# ece411-t17-thermal-hud.net
KiCad netlist of a schematic drawn in EAGLE
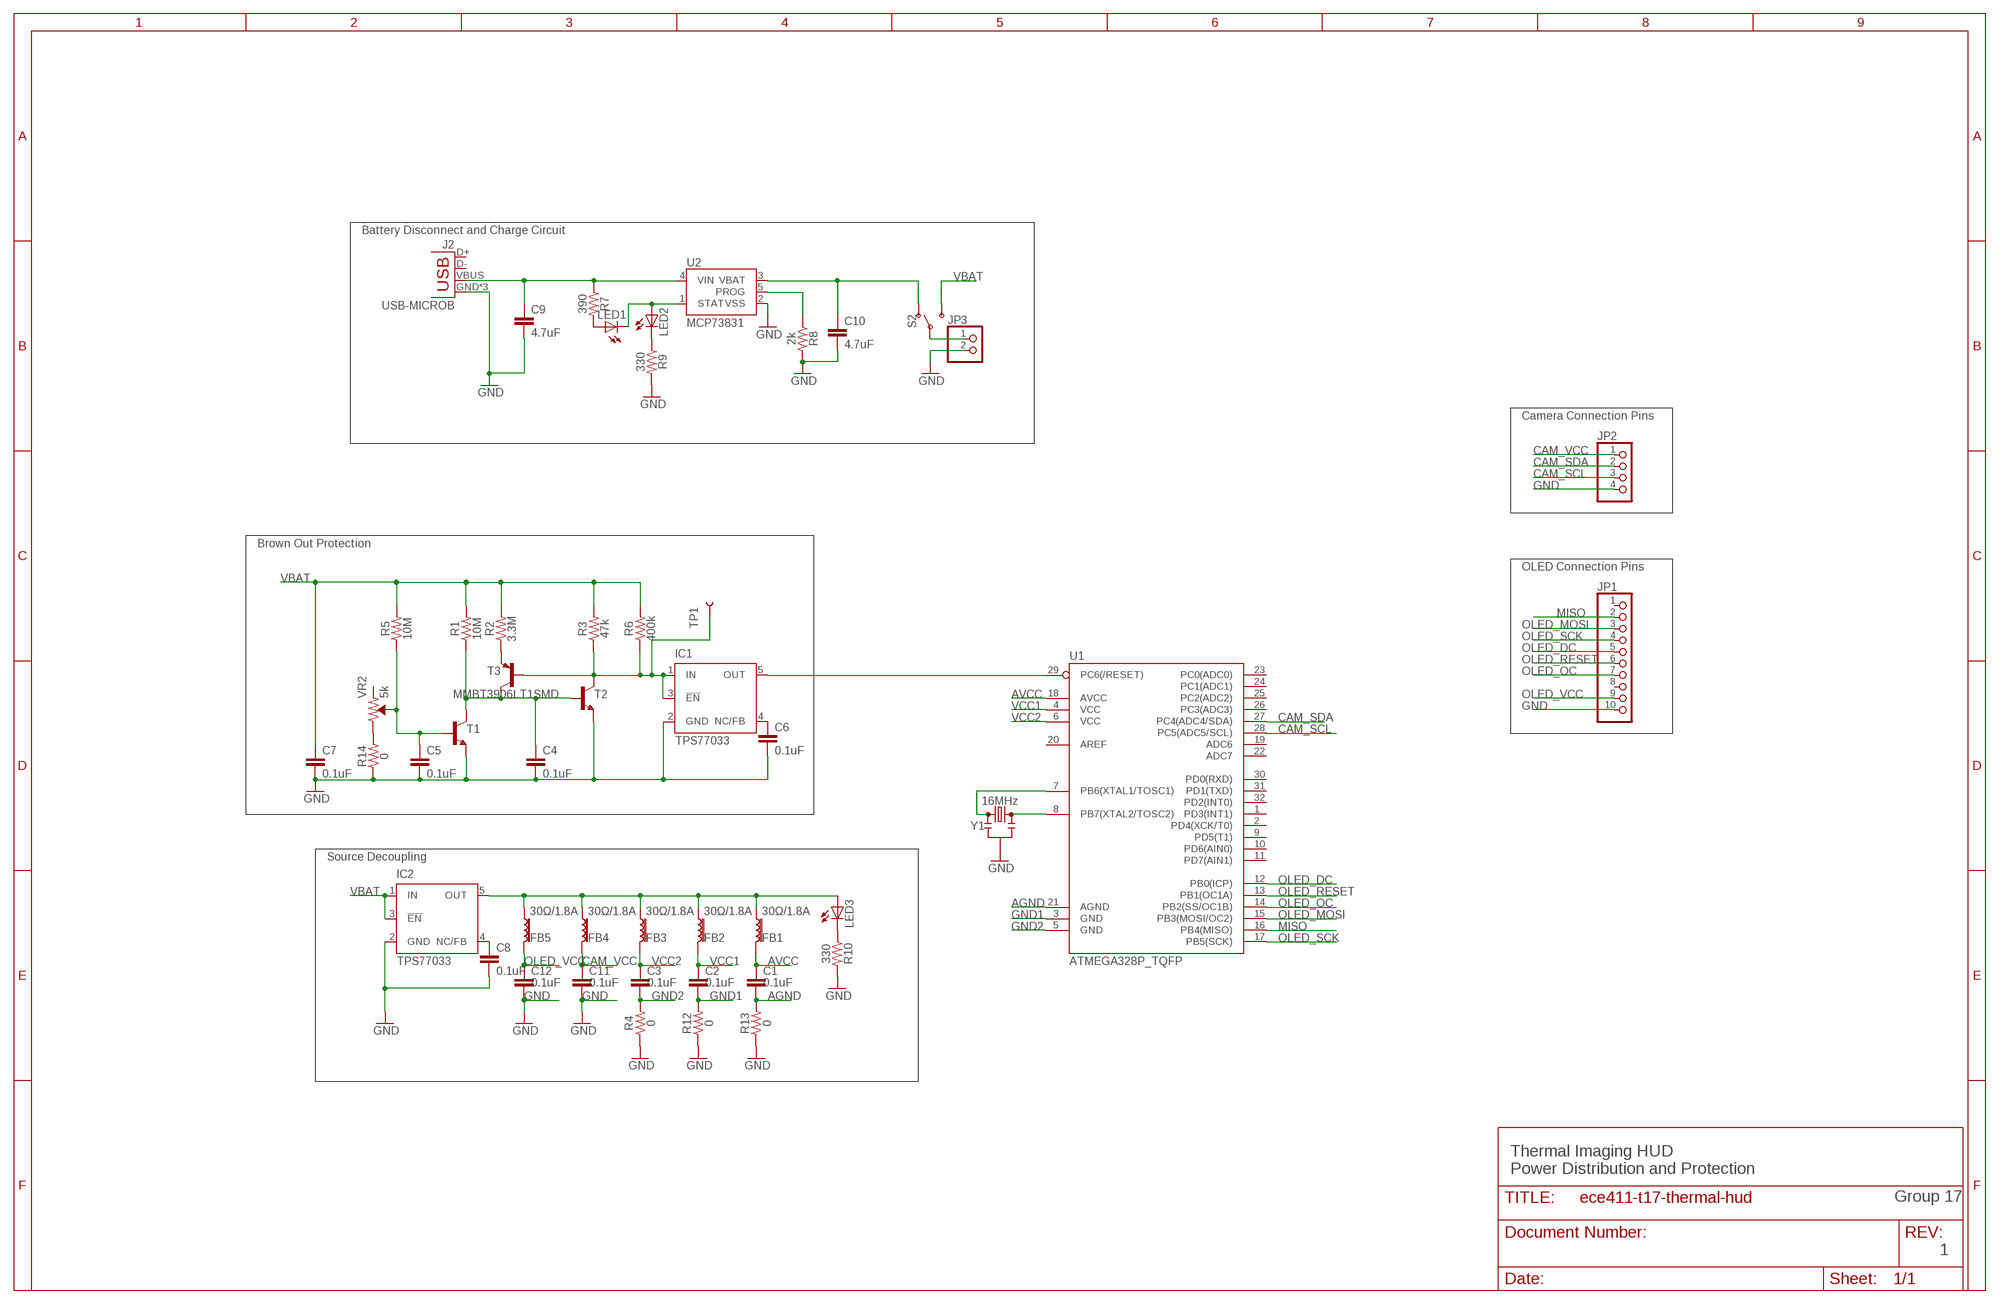
[diagram p0: schematic, sheet 1]

(export (version "E")
  (design (tool "Eeschema 10.0.6"))
  (components
    (comp (ref "C1")
      (value "0.1uF")
      (footprint "eagle-import:0603")
      (libsource (lib "eagle-import") (part "0.1UF-0603-25V-5%"))
    )
    (comp (ref "C2")
      (value "0.1uF")
      (footprint "eagle-import:0603")
      (libsource (lib "eagle-import") (part "0.1UF-0603-25V-5%"))
    )
    (comp (ref "C3")
      (value "0.1uF")
      (footprint "eagle-import:0603")
      (libsource (lib "eagle-import") (part "0.1UF-0603-25V-5%"))
    )
    (comp (ref "C4")
      (value "0.1uF")
      (footprint "eagle-import:0603")
      (libsource (lib "eagle-import") (part "0.1UF-0603-25V-5%"))
    )
    (comp (ref "C5")
      (value "0.1uF")
      (footprint "eagle-import:0603")
      (libsource (lib "eagle-import") (part "0.1UF-0603-25V-5%"))
    )
    (comp (ref "C6")
      (value "0.1uF")
      (footprint "eagle-import:0603")
      (libsource (lib "eagle-import") (part "0.1UF-0603-25V-5%"))
    )
    (comp (ref "C7")
      (value "0.1uF")
      (footprint "eagle-import:0603")
      (libsource (lib "eagle-import") (part "0.1UF-0603-25V-5%"))
    )
    (comp (ref "C8")
      (value "0.1uF")
      (footprint "eagle-import:0603")
      (libsource (lib "eagle-import") (part "0.1UF-0603-25V-5%"))
    )
    (comp (ref "C9")
      (value "4.7uF")
      (footprint "eagle-import:0603")
      (libsource (lib "eagle-import") (part "0.1UF-0603-25V-5%"))
    )
    (comp (ref "C10")
      (value "4.7uF")
      (footprint "eagle-import:0603")
      (libsource (lib "eagle-import") (part "0.1UF-0603-25V-5%"))
    )
    (comp (ref "C11")
      (value "0.1uF")
      (footprint "eagle-import:0603")
      (libsource (lib "eagle-import") (part "0.1UF-0603-25V-5%"))
    )
    (comp (ref "C12")
      (value "0.1uF")
      (footprint "eagle-import:0603")
      (libsource (lib "eagle-import") (part "0.1UF-0603-25V-5%"))
    )
    (comp (ref "FB1")
      (value "30Ω/1.8A")
      (footprint "eagle-import:0603")
      (libsource (lib "eagle-import") (part "FERRITE_BEAD-0603"))
    )
    (comp (ref "FB2")
      (value "30Ω/1.8A")
      (footprint "eagle-import:0603")
      (libsource (lib "eagle-import") (part "FERRITE_BEAD-0603"))
    )
    (comp (ref "FB3")
      (value "30Ω/1.8A")
      (footprint "eagle-import:0603")
      (libsource (lib "eagle-import") (part "FERRITE_BEAD-0603"))
    )
    (comp (ref "FB4")
      (value "30Ω/1.8A")
      (footprint "eagle-import:0603")
      (libsource (lib "eagle-import") (part "FERRITE_BEAD-0603"))
    )
    (comp (ref "FB5")
      (value "30Ω/1.8A")
      (footprint "eagle-import:0603")
      (libsource (lib "eagle-import") (part "FERRITE_BEAD-0603"))
    )
    (comp (ref "IC1")
      (value "TPS77033")
      (footprint "eagle-import:SOT23-DBV")
      (fields (field (name "MF") "TEXAS INSTRUMENTS") (field (name "MPN") "TPS77033DBVT"))
      (libsource (lib "eagle-import") (part "TPS77033"))
    )
    (comp (ref "IC2")
      (value "TPS77033")
      (footprint "eagle-import:SOT23-DBV")
      (fields (field (name "MF") "TEXAS INSTRUMENTS") (field (name "MPN") "TPS77033DBVT"))
      (libsource (lib "eagle-import") (part "TPS77033"))
    )
    (comp (ref "J2")
      (value "USB-MICROB")
      (footprint "eagle-import:USB-MICROB")
      (libsource (lib "eagle-import") (part "USB-MICROB"))
    )
    (comp (ref "JP1")
      (value "PINHD-1X10/90")
      (footprint "eagle-import:1X10_90")
      (libsource (lib "eagle-import") (part "PINHD-1X10/90"))
    )
    (comp (ref "JP2")
      (value "PINHD-1X4/90")
      (footprint "eagle-import:1X04_90")
      (libsource (lib "eagle-import") (part "PINHD-1X4/90"))
    )
    (comp (ref "JP3")
      (value "PINHD-1X2/90")
      (footprint "eagle-import:1X02_90")
      (libsource (lib "eagle-import") (part "PINHD-1X2/90"))
    )
    (comp (ref "LED1")
      (value "LEDCHIPLED_0603")
      (footprint "eagle-import:CHIPLED_0603")
      (libsource (lib "eagle-import") (part "LEDCHIPLED_0603"))
    )
    (comp (ref "LED2")
      (value "LEDCHIPLED_0603")
      (footprint "eagle-import:CHIPLED_0603")
      (libsource (lib "eagle-import") (part "LEDCHIPLED_0603"))
    )
    (comp (ref "LED3")
      (value "LEDCHIPLED_0603")
      (footprint "eagle-import:CHIPLED_0603")
      (libsource (lib "eagle-import") (part "LEDCHIPLED_0603"))
    )
    (comp (ref "R1")
      (value "10M")
      (footprint "eagle-import:0603")
      (libsource (lib "eagle-import") (part "10MOHM-0603-1/10W-5%"))
    )
    (comp (ref "R2")
      (value "3.3M")
      (footprint "eagle-import:0603")
      (libsource (lib "eagle-import") (part "10MOHM-0603-1/10W-5%"))
    )
    (comp (ref "R3")
      (value "47k")
      (footprint "eagle-import:0603")
      (libsource (lib "eagle-import") (part "10MOHM-0603-1/10W-5%"))
    )
    (comp (ref "R4")
      (value "0")
      (footprint "eagle-import:0603")
      (libsource (lib "eagle-import") (part "0OHM-0603-1/10W-5%"))
    )
    (comp (ref "R5")
      (value "10M")
      (footprint "eagle-import:0603")
      (libsource (lib "eagle-import") (part "10MOHM-0603-1/10W-5%"))
    )
    (comp (ref "R6")
      (value "400k")
      (footprint "eagle-import:0603")
      (libsource (lib "eagle-import") (part "10MOHM-0603-1/10W-5%"))
    )
    (comp (ref "R7")
      (value "390")
      (footprint "eagle-import:0603")
      (libsource (lib "eagle-import") (part "10MOHM-0603-1/10W-5%"))
    )
    (comp (ref "R8")
      (value "2k")
      (footprint "eagle-import:0603")
      (libsource (lib "eagle-import") (part "10MOHM-0603-1/10W-5%"))
    )
    (comp (ref "R9")
      (value "330")
      (footprint "eagle-import:0603")
      (libsource (lib "eagle-import") (part "10MOHM-0603-1/10W-5%"))
    )
    (comp (ref "R10")
      (value "330")
      (footprint "eagle-import:0603")
      (libsource (lib "eagle-import") (part "10MOHM-0603-1/10W-5%"))
    )
    (comp (ref "R12")
      (value "0")
      (footprint "eagle-import:0603")
      (libsource (lib "eagle-import") (part "0OHM-0603-1/10W-5%"))
    )
    (comp (ref "R13")
      (value "0")
      (footprint "eagle-import:0603")
      (libsource (lib "eagle-import") (part "0OHM-0603-1/10W-5%"))
    )
    (comp (ref "R14")
      (value "0")
      (footprint "eagle-import:0603")
      (libsource (lib "eagle-import") (part "0OHM-0603-1/10W-5%"))
    )
    (comp (ref "S2")
      (value "SWITCH-SPDT-PTH-11.6X4.0MM")
      (footprint "eagle-import:SWITCH_SPDT_PTH_11.6X4.0MM")
      (libsource (lib "eagle-import") (part "SWITCH-SPDT-PTH-11.6X4.0MM"))
    )
    (comp (ref "T1")
      (value "MMBT3904LT1-NPN-SOT23-BEC")
      (footprint "eagle-import:SOT23-BEC")
      (libsource (lib "eagle-import") (part "-NPN-SOT23-BECMMBT3904LT1"))
    )
    (comp (ref "T2")
      (value "MMBT3904LT1-NPN-SOT23-BEC")
      (footprint "eagle-import:SOT23-BEC")
      (libsource (lib "eagle-import") (part "-NPN-SOT23-BECMMBT3904LT1"))
    )
    (comp (ref "T3")
      (value "MMBT3906LT1SMD")
      (footprint "eagle-import:SOT23-BEC")
      (libsource (lib "eagle-import") (part "MMBT3906SMDLT1"))
    )
    (comp (ref "TP1")
      (value "TEST-POINT3X5")
      (footprint "eagle-import:PAD.03X.05")
      (libsource (lib "eagle-import") (part "TEST-POINT3X5"))
    )
    (comp (ref "U1")
      (value "ATMEGA328P_TQFP")
      (footprint "eagle-import:TQFP32-08")
      (libsource (lib "eagle-import") (part "ATMEGA328P_TQFP"))
    )
    (comp (ref "U2")
      (value "MCP73831")
      (footprint "eagle-import:SOT23-5")
      (libsource (lib "eagle-import") (part "MCP73831"))
    )
    (comp (ref "VR2")
      (value "5k")
      (footprint "eagle-import:TRIMPOT-SMD-5MM")
      (libsource (lib "eagle-import") (part "TRIMPOT-SMD-5MM-CLOSED-1/4W-20%"))
    )
    (comp (ref "Y1")
      (value "16MHz")
      (footprint "eagle-import:RESONATOR-SMD-3.2X1.3")
      (libsource (lib "eagle-import") (part "RESONATOR-16MHZSMD_3.2X1.3"))
    )
  )
  (nets
    (net (code "1") (name "/AGND") (class "Default")
      (node (ref "C1") (pin "2") (pinfunction "2_2") (pintype "passive"))
      (node (ref "R13") (pin "2") (pinfunction "2_2") (pintype "passive"))
      (node (ref "U1") (pin "21") (pinfunction "AGND_21") (pintype "bidirectional"))
    )
    (net (code "2") (name "/AVCC") (class "Default")
      (node (ref "C1") (pin "1") (pinfunction "1_1") (pintype "passive"))
      (node (ref "FB1") (pin "2") (pinfunction "2_2") (pintype "passive"))
      (node (ref "U1") (pin "18") (pinfunction "AVCC_18") (pintype "bidirectional"))
    )
    (net (code "3") (name "/CAM_SCL") (class "Default")
      (node (ref "JP2") (pin "3") (pinfunction "3_3") (pintype "passive"))
      (node (ref "U1") (pin "28") (pinfunction "PC5(ADC5/SCL)_28") (pintype "bidirectional"))
    )
    (net (code "4") (name "/CAM_SDA") (class "Default")
      (node (ref "JP2") (pin "2") (pinfunction "2_2") (pintype "passive"))
      (node (ref "U1") (pin "27") (pinfunction "PC4(ADC4/SDA)_27") (pintype "bidirectional"))
    )
    (net (code "5") (name "/CAM_VCC") (class "Default")
      (node (ref "C11") (pin "1") (pinfunction "1_1") (pintype "passive"))
      (node (ref "FB4") (pin "2") (pinfunction "2_2") (pintype "passive"))
      (node (ref "JP2") (pin "1") (pinfunction "1_1") (pintype "passive"))
    )
    (net (code "6") (name "/GND1") (class "Default")
      (node (ref "C2") (pin "2") (pinfunction "2_2") (pintype "passive"))
      (node (ref "R12") (pin "2") (pinfunction "2_2") (pintype "passive"))
      (node (ref "U1") (pin "3") (pinfunction "GND_3") (pintype "bidirectional"))
    )
    (net (code "7") (name "/GND2") (class "Default")
      (node (ref "C3") (pin "2") (pinfunction "2_2") (pintype "passive"))
      (node (ref "R4") (pin "2") (pinfunction "2_2") (pintype "passive"))
      (node (ref "U1") (pin "5") (pinfunction "GND_5") (pintype "bidirectional"))
    )
    (net (code "8") (name "/MISO") (class "Default")
      (node (ref "JP1") (pin "2") (pinfunction "2_2") (pintype "passive"))
      (node (ref "U1") (pin "16") (pinfunction "PB4(MISO)_16") (pintype "bidirectional"))
    )
    (net (code "9") (name "/OLED_DC") (class "Default")
      (node (ref "JP1") (pin "5") (pinfunction "5_5") (pintype "passive"))
      (node (ref "U1") (pin "12") (pinfunction "PB0(ICP)_12") (pintype "bidirectional"))
    )
    (net (code "10") (name "/OLED_MOSI") (class "Default")
      (node (ref "JP1") (pin "3") (pinfunction "3_3") (pintype "passive"))
      (node (ref "U1") (pin "15") (pinfunction "PB3(MOSI/OC2)_15") (pintype "bidirectional"))
    )
    (net (code "11") (name "/OLED_OC") (class "Default")
      (node (ref "JP1") (pin "7") (pinfunction "7_7") (pintype "passive"))
      (node (ref "U1") (pin "14") (pinfunction "PB2(SS/OC1B)_14") (pintype "bidirectional"))
    )
    (net (code "12") (name "/OLED_RESET") (class "Default")
      (node (ref "JP1") (pin "6") (pinfunction "6_6") (pintype "passive"))
      (node (ref "U1") (pin "13") (pinfunction "PB1(OC1A)_13") (pintype "bidirectional"))
    )
    (net (code "13") (name "/OLED_SCK") (class "Default")
      (node (ref "JP1") (pin "4") (pinfunction "4_4") (pintype "passive"))
      (node (ref "U1") (pin "17") (pinfunction "PB5(SCK)_17") (pintype "bidirectional"))
    )
    (net (code "14") (name "/OLED_VCC") (class "Default")
      (node (ref "C12") (pin "1") (pinfunction "1_1") (pintype "passive"))
      (node (ref "FB5") (pin "2") (pinfunction "2_2") (pintype "passive"))
      (node (ref "JP1") (pin "9") (pinfunction "9_9") (pintype "passive"))
    )
    (net (code "15") (name "/VBAT") (class "Default")
      (node (ref "C7") (pin "1") (pinfunction "1_1") (pintype "passive"))
      (node (ref "IC2") (pin "1") (pinfunction "IN_1") (pintype "input"))
      (node (ref "IC2") (pin "3") (pinfunction "~{EN}_3") (pintype "input"))
      (node (ref "R1") (pin "2") (pinfunction "2_2") (pintype "passive"))
      (node (ref "R2") (pin "2") (pinfunction "2_2") (pintype "passive"))
      (node (ref "R3") (pin "2") (pinfunction "2_2") (pintype "passive"))
      (node (ref "R5") (pin "2") (pinfunction "2_2") (pintype "passive"))
      (node (ref "R6") (pin "2") (pinfunction "2_2") (pintype "passive"))
      (node (ref "S2") (pin "3") (pinfunction "S_3") (pintype "passive"))
    )
    (net (code "16") (name "/VCC1") (class "Default")
      (node (ref "C2") (pin "1") (pinfunction "1_1") (pintype "passive"))
      (node (ref "FB2") (pin "2") (pinfunction "2_2") (pintype "passive"))
      (node (ref "U1") (pin "4") (pinfunction "VCC_4") (pintype "bidirectional"))
    )
    (net (code "17") (name "/VCC2") (class "Default")
      (node (ref "C3") (pin "1") (pinfunction "1_1") (pintype "passive"))
      (node (ref "FB3") (pin "2") (pinfunction "2_2") (pintype "passive"))
      (node (ref "U1") (pin "6") (pinfunction "VCC_6") (pintype "bidirectional"))
    )
    (net (code "18") (name "GND") (class "Default")
      (node (ref "C10") (pin "2") (pinfunction "2_2") (pintype "passive"))
      (node (ref "C11") (pin "2") (pinfunction "2_2") (pintype "passive"))
      (node (ref "C12") (pin "2") (pinfunction "2_2") (pintype "passive"))
      (node (ref "C4") (pin "2") (pinfunction "2_2") (pintype "passive"))
      (node (ref "C5") (pin "2") (pinfunction "2_2") (pintype "passive"))
      (node (ref "C6") (pin "2") (pinfunction "2_2") (pintype "passive"))
      (node (ref "C7") (pin "2") (pinfunction "2_2") (pintype "passive"))
      (node (ref "C8") (pin "2") (pinfunction "2_2") (pintype "passive"))
      (node (ref "C9") (pin "2") (pinfunction "2_2") (pintype "passive"))
      (node (ref "IC1") (pin "2") (pinfunction "GND_2") (pintype "power_in"))
      (node (ref "IC2") (pin "2") (pinfunction "GND_2") (pintype "power_in"))
      (node (ref "J2") (pin "GND") (pinfunction "GND_GND") (pintype "bidirectional"))
      (node (ref "J2") (pin "MT1") (pinfunction "GND_MT1") (pintype "bidirectional"))
      (node (ref "J2") (pin "MT2") (pinfunction "GND_MT2") (pintype "bidirectional"))
      (node (ref "JP1") (pin "10") (pinfunction "10_10") (pintype "passive"))
      (node (ref "JP2") (pin "4") (pinfunction "4_4") (pintype "passive"))
      (node (ref "JP3") (pin "2") (pinfunction "2_2") (pintype "passive"))
      (node (ref "R10") (pin "2") (pinfunction "2_2") (pintype "passive"))
      (node (ref "R12") (pin "1") (pinfunction "1_1") (pintype "passive"))
      (node (ref "R13") (pin "1") (pinfunction "1_1") (pintype "passive"))
      (node (ref "R14") (pin "1") (pinfunction "1_1") (pintype "passive"))
      (node (ref "R4") (pin "1") (pinfunction "1_1") (pintype "passive"))
      (node (ref "R8") (pin "2") (pinfunction "2_2") (pintype "passive"))
      (node (ref "R9") (pin "2") (pinfunction "2_2") (pintype "passive"))
      (node (ref "T1") (pin "E") (pinfunction "E_E") (pintype "passive"))
      (node (ref "T2") (pin "E") (pinfunction "E_E") (pintype "passive"))
      (node (ref "U2") (pin "2") (pinfunction "VSS_2") (pintype "power_in"))
      (node (ref "Y1") (pin "2") (pinfunction "2_2") (pintype "passive"))
    )
    (net (code "19") (name "Net-(C4-Pad1)") (class "Default")
      (node (ref "C4") (pin "1") (pinfunction "1_1") (pintype "passive"))
      (node (ref "R1") (pin "1") (pinfunction "1_1") (pintype "passive"))
      (node (ref "T1") (pin "C") (pinfunction "C_C") (pintype "passive"))
      (node (ref "T2") (pin "B") (pinfunction "B_B") (pintype "passive"))
      (node (ref "T3") (pin "C") (pinfunction "C_C") (pintype "passive"))
    )
    (net (code "20") (name "Net-(IC1-IN)") (class "Default")
      (node (ref "IC1") (pin "1") (pinfunction "IN_1") (pintype "input"))
      (node (ref "IC1") (pin "3") (pinfunction "~{EN}_3") (pintype "input"))
      (node (ref "R3") (pin "1") (pinfunction "1_1") (pintype "passive"))
      (node (ref "R6") (pin "1") (pinfunction "1_1") (pintype "passive"))
      (node (ref "T2") (pin "C") (pinfunction "C_C") (pintype "passive"))
      (node (ref "T3") (pin "B") (pinfunction "B_B") (pintype "passive"))
      (node (ref "TP1") (pin "P$1") (pinfunction "1_P$1") (pintype "bidirectional"))
    )
    (net (code "21") (name "Net-(IC1-NC{slash}FB)") (class "Default")
      (node (ref "C6") (pin "1") (pinfunction "1_1") (pintype "passive"))
      (node (ref "IC1") (pin "4") (pinfunction "NC/FB_4") (pintype "passive"))
    )
    (net (code "22") (name "Net-(IC1-OUT)") (class "Default")
      (node (ref "IC1") (pin "5") (pinfunction "OUT_5") (pintype "passive"))
      (node (ref "U1") (pin "29") (pinfunction "PC6(/RESET)_29") (pintype "bidirectional"))
    )
    (net (code "23") (name "Net-(IC2-NC{slash}FB)") (class "Default")
      (node (ref "C8") (pin "1") (pinfunction "1_1") (pintype "passive"))
      (node (ref "IC2") (pin "4") (pinfunction "NC/FB_4") (pintype "passive"))
    )
    (net (code "24") (name "Net-(IC2-OUT)") (class "Default")
      (node (ref "FB1") (pin "1") (pinfunction "1_1") (pintype "passive"))
      (node (ref "FB2") (pin "1") (pinfunction "1_1") (pintype "passive"))
      (node (ref "FB3") (pin "1") (pinfunction "1_1") (pintype "passive"))
      (node (ref "FB4") (pin "1") (pinfunction "1_1") (pintype "passive"))
      (node (ref "FB5") (pin "1") (pinfunction "1_1") (pintype "passive"))
      (node (ref "IC2") (pin "5") (pinfunction "OUT_5") (pintype "passive"))
      (node (ref "LED3") (pin "A") (pinfunction "A_A") (pintype "passive"))
    )
    (net (code "25") (name "Net-(LED1-PadA)") (class "Default")
      (node (ref "LED1") (pin "A") (pinfunction "A_A") (pintype "passive"))
      (node (ref "R7") (pin "2") (pinfunction "2_2") (pintype "passive"))
    )
    (net (code "26") (name "Net-(LED2-PadC)") (class "Default")
      (node (ref "LED2") (pin "C") (pinfunction "C_C") (pintype "passive"))
      (node (ref "R9") (pin "1") (pinfunction "1_1") (pintype "passive"))
    )
    (net (code "27") (name "Net-(LED3-PadC)") (class "Default")
      (node (ref "LED3") (pin "C") (pinfunction "C_C") (pintype "passive"))
      (node (ref "R10") (pin "1") (pinfunction "1_1") (pintype "passive"))
    )
    (net (code "28") (name "Net-(R2-Pad1)") (class "Default")
      (node (ref "R2") (pin "1") (pinfunction "1_1") (pintype "passive"))
      (node (ref "T3") (pin "E") (pinfunction "E_E") (pintype "passive"))
    )
    (net (code "29") (name "Net-(S2-O)") (class "Default")
      (node (ref "C10") (pin "1") (pinfunction "1_1") (pintype "passive"))
      (node (ref "S2") (pin "1") (pinfunction "O_1") (pintype "passive"))
      (node (ref "U2") (pin "3") (pinfunction "VBAT_3") (pintype "power_in"))
    )
    (net (code "30") (name "Net-(S2-P)") (class "Default")
      (node (ref "JP3") (pin "1") (pinfunction "1_1") (pintype "passive"))
      (node (ref "S2") (pin "2") (pinfunction "P_2") (pintype "passive"))
    )
    (net (code "31") (name "Net-(U1-PB6(XTAL1{slash}TOSC1))") (class "Default")
      (node (ref "U1") (pin "7") (pinfunction "PB6(XTAL1/TOSC1)_7") (pintype "bidirectional"))
      (node (ref "Y1") (pin "1") (pinfunction "1_1") (pintype "passive"))
    )
    (net (code "32") (name "Net-(U1-PB7(XTAL2{slash}TOSC2))") (class "Default")
      (node (ref "U1") (pin "8") (pinfunction "PB7(XTAL2/TOSC2)_8") (pintype "bidirectional"))
      (node (ref "Y1") (pin "3") (pinfunction "3_3") (pintype "passive"))
    )
    (net (code "33") (name "Net-(U2-PROG)") (class "Default")
      (node (ref "R8") (pin "1") (pinfunction "1_1") (pintype "passive"))
      (node (ref "U2") (pin "5") (pinfunction "PROG_5") (pintype "input"))
    )
    (net (code "34") (name "Net-(U2-STAT)") (class "Default")
      (node (ref "LED1") (pin "C") (pinfunction "C_C") (pintype "passive"))
      (node (ref "LED2") (pin "A") (pinfunction "A_A") (pintype "passive"))
      (node (ref "U2") (pin "1") (pinfunction "STAT_1") (pintype "output"))
    )
    (net (code "35") (name "Net-(U2-VIN)") (class "Default")
      (node (ref "C9") (pin "1") (pinfunction "1_1") (pintype "passive"))
      (node (ref "J2") (pin "VBUS") (pinfunction "VBUS_VBUS") (pintype "bidirectional"))
      (node (ref "R7") (pin "1") (pinfunction "1_1") (pintype "passive"))
      (node (ref "U2") (pin "4") (pinfunction "VIN_4") (pintype "power_in"))
    )
    (net (code "36") (name "Net-(VR2-CW)") (class "Default")
      (node (ref "R14") (pin "2") (pinfunction "2_2") (pintype "passive"))
      (node (ref "VR2") (pin "C") (pinfunction "CW_C") (pintype "passive"))
    )
    (net (code "37") (name "Net-(VR2-WIPER)") (class "Default")
      (node (ref "C5") (pin "1") (pinfunction "1_1") (pintype "passive"))
      (node (ref "R5") (pin "1") (pinfunction "1_1") (pintype "passive"))
      (node (ref "T1") (pin "B") (pinfunction "B_B") (pintype "passive"))
      (node (ref "VR2") (pin "B") (pinfunction "WIPER_B") (pintype "passive"))
    )
    (net (code "38") (name "unconnected-(J2-PadD+)") (class "Default")
      (node (ref "J2") (pin "D+") (pinfunction "D+_D+") (pintype "bidirectional"))
    )
    (net (code "39") (name "unconnected-(J2-PadD-)") (class "Default")
      (node (ref "J2") (pin "D-") (pinfunction "D-_D-") (pintype "bidirectional"))
    )
    (net (code "40") (name "unconnected-(JP1-Pad1)") (class "Default")
      (node (ref "JP1") (pin "1") (pinfunction "1_1") (pintype "passive"))
    )
    (net (code "41") (name "unconnected-(JP1-Pad8)") (class "Default")
      (node (ref "JP1") (pin "8") (pinfunction "8_8") (pintype "passive"))
    )
    (net (code "42") (name "unconnected-(U1-ADC6-Pad19)") (class "Default")
      (node (ref "U1") (pin "19") (pinfunction "ADC6_19") (pintype "bidirectional"))
    )
    (net (code "43") (name "unconnected-(U1-ADC7-Pad22)") (class "Default")
      (node (ref "U1") (pin "22") (pinfunction "ADC7_22") (pintype "bidirectional"))
    )
    (net (code "44") (name "unconnected-(U1-AREF-Pad20)") (class "Default")
      (node (ref "U1") (pin "20") (pinfunction "AREF_20") (pintype "bidirectional"))
    )
    (net (code "45") (name "unconnected-(U1-PC0(ADC0)-Pad23)") (class "Default")
      (node (ref "U1") (pin "23") (pinfunction "PC0(ADC0)_23") (pintype "bidirectional"))
    )
    (net (code "46") (name "unconnected-(U1-PC1(ADC1)-Pad24)") (class "Default")
      (node (ref "U1") (pin "24") (pinfunction "PC1(ADC1)_24") (pintype "bidirectional"))
    )
    (net (code "47") (name "unconnected-(U1-PC2(ADC2)-Pad25)") (class "Default")
      (node (ref "U1") (pin "25") (pinfunction "PC2(ADC2)_25") (pintype "bidirectional"))
    )
    (net (code "48") (name "unconnected-(U1-PC3(ADC3)-Pad26)") (class "Default")
      (node (ref "U1") (pin "26") (pinfunction "PC3(ADC3)_26") (pintype "bidirectional"))
    )
    (net (code "49") (name "unconnected-(U1-PD0(RXD)-Pad30)") (class "Default")
      (node (ref "U1") (pin "30") (pinfunction "PD0(RXD)_30") (pintype "bidirectional"))
    )
    (net (code "50") (name "unconnected-(U1-PD1(TXD)-Pad31)") (class "Default")
      (node (ref "U1") (pin "31") (pinfunction "PD1(TXD)_31") (pintype "bidirectional"))
    )
    (net (code "51") (name "unconnected-(U1-PD2(INT0)-Pad32)") (class "Default")
      (node (ref "U1") (pin "32") (pinfunction "PD2(INT0)_32") (pintype "bidirectional"))
    )
    (net (code "52") (name "unconnected-(U1-PD3(INT1)-Pad1)") (class "Default")
      (node (ref "U1") (pin "1") (pinfunction "PD3(INT1)_1") (pintype "bidirectional"))
    )
    (net (code "53") (name "unconnected-(U1-PD4(XCK{slash}T0)-Pad2)") (class "Default")
      (node (ref "U1") (pin "2") (pinfunction "PD4(XCK/T0)_2") (pintype "bidirectional"))
    )
    (net (code "54") (name "unconnected-(U1-PD5(T1)-Pad9)") (class "Default")
      (node (ref "U1") (pin "9") (pinfunction "PD5(T1)_9") (pintype "bidirectional"))
    )
    (net (code "55") (name "unconnected-(U1-PD6(AIN0)-Pad10)") (class "Default")
      (node (ref "U1") (pin "10") (pinfunction "PD6(AIN0)_10") (pintype "bidirectional"))
    )
    (net (code "56") (name "unconnected-(U1-PD7(AIN1)-Pad11)") (class "Default")
      (node (ref "U1") (pin "11") (pinfunction "PD7(AIN1)_11") (pintype "bidirectional"))
    )
    (net (code "57") (name "unconnected-(VR2-CCW-PadA)") (class "Default")
      (node (ref "VR2") (pin "A") (pinfunction "CCW_A") (pintype "passive"))
    )
  )
)
